# Power.net
KiCad netlist of a schematic drawn in Altium Designer
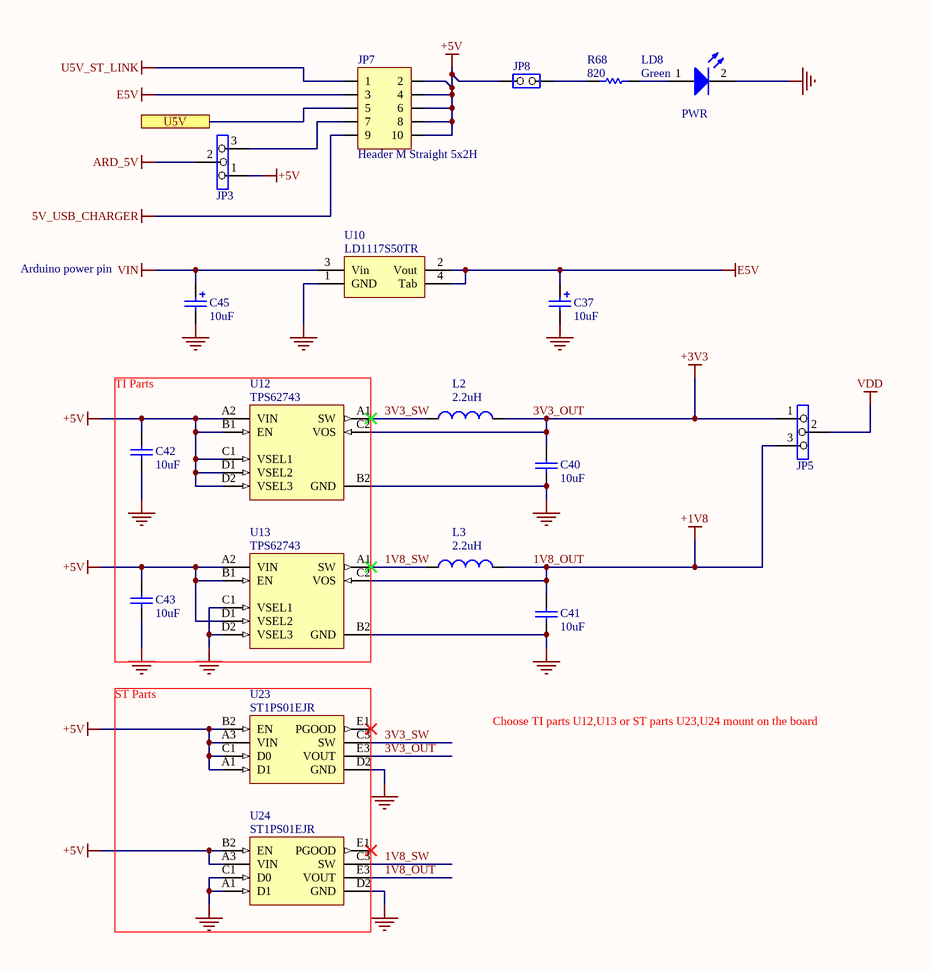
[diagram p0: Power.SchDoc]

(export (version "E")
  (design (tool "Eeschema 10.0.6"))
  (components
    (comp (ref "C37")
      (value "10uF")
      (footprint "TAN-A")
      (description "TAN Capacitor,10uF,10%,16V,A Type,AVX")
      (fields (field (name "Comment") "TAJA106K016R") (field (name "PUBLISHER") "Altium Limited"))
      (libsource (lib "Miscellaneous Devices") (part "Cap Pol1"))
    )
    (comp (ref "C40")
      (value "10uF")
      (footprint "0402C")
      (description "Capacitor,10uF,0402,GRM155R60J106ME11")
      (fields (field (name "Comment") "GRM155R60J106ME11") (field (name "PUBLISHER") "Altium Limited"))
      (libsource (lib "Miscellaneous Devices") (part "Cap"))
    )
    (comp (ref "C41")
      (value "10uF")
      (footprint "0402C")
      (description "Capacitor,10uF,0402,GRM155R60J106ME11")
      (fields (field (name "Comment") "GRM155R60J106ME11") (field (name "PUBLISHER") "Altium Limited"))
      (libsource (lib "Miscellaneous Devices") (part "Cap"))
    )
    (comp (ref "C42")
      (value "10uF")
      (footprint "0402C")
      (description "Capacitor,10uF,0402,GRM155R60J106ME11")
      (fields (field (name "Comment") "GRM155R60J106ME11") (field (name "PUBLISHER") "Altium Limited"))
      (libsource (lib "Miscellaneous Devices") (part "Cap"))
    )
    (comp (ref "C43")
      (value "10uF")
      (footprint "0402C")
      (description "Capacitor,10uF,0402,GRM155R60J106ME11")
      (fields (field (name "Comment") "GRM155R60J106ME11") (field (name "PUBLISHER") "Altium Limited"))
      (libsource (lib "Miscellaneous Devices") (part "Cap"))
    )
    (comp (ref "C45")
      (value "10uF")
      (footprint "TAN-B")
      (description "Tan Capacitor,10uF,10%,25V,Tan-B,TAJB106K025RNJ")
      (fields (field (name "Comment") "TAJB106K025RNJ") (field (name "PUBLISHER") "Altium Limited"))
      (libsource (lib "Miscellaneous Devices") (part "Cap Pol1"))
    )
    (comp (ref "JP3")
      (value "3 PIN Jumper")
      (footprint "SIP3")
      (libsource (lib "STR910_SCHLIB") (part "Jumper3"))
    )
    (comp (ref "JP5")
      (value "3 PIN Jumper")
      (footprint "SIP3")
      (libsource (lib "STR910_SCHLIB") (part "Jumper3"))
    )
    (comp (ref "JP7")
      (value "Header M Straight 5x2H")
      (footprint "HDR_2X5_2R54")
      (description "Pin Header male,2.54mm,2*5,L=11.6,180,1U,DIP")
      (libsource (lib "MCD_TOOLS_CONNECTOR") (part "Header 5X2M"))
    )
    (comp (ref "JP8") (value "2 PIN Jumper") (footprint "SIP2") (libsource (lib "*") (part "JP2")))
    (comp (ref "L2")
      (value "2.2uH")
      (footprint "L1008_L0805_CPT")
      (description "Inductor")
      (fields (field (name "PUBLISHER") "Altium Limited"))
      (libsource (lib "Miscellaneous Devices") (part "Inductor"))
    )
    (comp (ref "L3")
      (value "2.2uH")
      (footprint "L1008_L0805_CPT")
      (description "Inductor")
      (fields (field (name "PUBLISHER") "Altium Limited"))
      (libsource (lib "Miscellaneous Devices") (part "Inductor"))
    )
    (comp (ref "LD8")
      (value "19-213SY6C/S530-E2/TR8LED")
      (footprint "0603D")
      (description "LED,Green,0603")
      (fields
        (field (name "SILKSCREEN") "PWR")
        (field (name "CORLOR") "Green")
        (field (name "PUBLISHER") "Altium Limited")
      )
      (libsource (lib "Miscellaneous Devices") (part "LED2"))
    )
    (comp (ref "R68")
      (value "820")
      (footprint "0603R")
      (description "Resistor")
      (fields (field (name "PUBLISHER") "Altium Limited"))
      (libsource (lib "Miscellaneous Devices") (part "res1"))
    )
    (comp (ref "U10")
      (value "LD1117S50TR")
      (footprint "SOT-223")
      (description "Adjustable and fixed low drop positive voltage regulator")
      (libsource (lib "MB1219") (part "LD1117S18TR"))
    )
    (comp (ref "U12")
      (value "TPS62743")
      (footprint "BGA8_0R4_0R9X1R6")
      (description "High Efficiency Buck Converter")
      (libsource (lib "MB1261") (part "TPS62743"))
    )
    (comp (ref "U13")
      (value "TPS62743")
      (footprint "BGA8_0R4_0R9X1R6")
      (description "High Efficiency Buck Converter")
      (libsource (lib "MB1261") (part "TPS62743"))
    )
    (comp (ref "U23")
      (value "ST1PS01EJR")
      (footprint "BGA8_0R312-0R25_1R11X1R41")
      (description "400mA NanoQuiescent Step Down converter")
      (libsource (lib "Big Orga") (part "ST1PS01EJR"))
    )
    (comp (ref "U24")
      (value "ST1PS01EJR")
      (footprint "BGA8_0R312-0R25_1R11X1R41")
      (description "400mA NanoQuiescent Step Down converter")
      (libsource (lib "Big Orga") (part "ST1PS01EJR"))
    )
  )
  (nets
    (net (code "1") (name "+1V8") (class "Default")
      (node (ref "C41") (pin "1") (pinfunction "1_1") (pintype "passive"))
      (node (ref "JP5") (pin "3") (pintype "passive"))
      (node (ref "L3") (pin "2") (pinfunction "2_2") (pintype "passive"))
      (node (ref "U13") (pin "C2") (pinfunction "VOS_C2") (pintype "input"))
      (node (ref "U24") (pin "E3") (pinfunction "VOUT_E3") (pintype "power_in"))
    )
    (net (code "2") (name "+3V3") (class "Default")
      (node (ref "C40") (pin "1") (pinfunction "1_1") (pintype "passive"))
      (node (ref "JP5") (pin "1") (pintype "passive"))
      (node (ref "L2") (pin "2") (pinfunction "2_2") (pintype "passive"))
      (node (ref "U12") (pin "C2") (pinfunction "VOS_C2") (pintype "input"))
      (node (ref "U23") (pin "E3") (pinfunction "VOUT_E3") (pintype "power_in"))
    )
    (net (code "3") (name "+5V") (class "Default")
      (node (ref "C42") (pin "1") (pinfunction "1_1") (pintype "passive"))
      (node (ref "C43") (pin "1") (pinfunction "1_1") (pintype "passive"))
      (node (ref "JP3") (pin "1") (pintype "passive"))
      (node (ref "JP7") (pin "10") (pinfunction "10_10") (pintype "passive"))
      (node (ref "JP7") (pin "2") (pinfunction "2_2") (pintype "passive"))
      (node (ref "JP7") (pin "4") (pinfunction "4_4") (pintype "passive"))
      (node (ref "JP7") (pin "6") (pinfunction "6_6") (pintype "passive"))
      (node (ref "JP7") (pin "8") (pinfunction "8_8") (pintype "passive"))
      (node (ref "JP8") (pin "1") (pinfunction "COMMON_1") (pintype "passive"))
      (node (ref "U12") (pin "A2") (pinfunction "VIN_A2") (pintype "power_in"))
      (node (ref "U12") (pin "B1") (pinfunction "EN_B1") (pintype "input"))
      (node (ref "U12") (pin "C1") (pinfunction "VSEL1_C1") (pintype "input"))
      (node (ref "U12") (pin "D1") (pinfunction "VSEL2_D1") (pintype "input"))
      (node (ref "U12") (pin "D2") (pinfunction "VSEL3_D2") (pintype "input"))
      (node (ref "U13") (pin "A2") (pinfunction "VIN_A2") (pintype "power_in"))
      (node (ref "U13") (pin "B1") (pinfunction "EN_B1") (pintype "input"))
      (node (ref "U13") (pin "D1") (pinfunction "VSEL2_D1") (pintype "input"))
      (node (ref "U23") (pin "A1") (pinfunction "D1_A1") (pintype "input"))
      (node (ref "U23") (pin "A3") (pinfunction "VIN_A3") (pintype "power_in"))
      (node (ref "U23") (pin "B2") (pinfunction "EN_B2") (pintype "input"))
      (node (ref "U23") (pin "C1") (pinfunction "D0_C1") (pintype "input"))
      (node (ref "U24") (pin "A3") (pinfunction "VIN_A3") (pintype "power_in"))
      (node (ref "U24") (pin "B2") (pinfunction "EN_B2") (pintype "input"))
    )
    (net (code "4") (name "/1V8_SW") (class "Default")
      (node (ref "L3") (pin "1") (pinfunction "1_1") (pintype "passive"))
      (node (ref "U13") (pin "A1") (pinfunction "SW_A1") (pintype "output"))
      (node (ref "U24") (pin "C3") (pinfunction "SW_C3") (pintype "power_in"))
    )
    (net (code "5") (name "/3V3_SW") (class "Default")
      (node (ref "L2") (pin "1") (pinfunction "1_1") (pintype "passive"))
      (node (ref "U12") (pin "A1") (pinfunction "SW_A1") (pintype "output"))
      (node (ref "U23") (pin "C3") (pinfunction "SW_C3") (pintype "power_in"))
    )
    (net (code "6") (name "/U5V") (class "Default")
      (node (ref "JP7") (pin "5") (pinfunction "5_5") (pintype "passive"))
    )
    (net (code "7") (name "5V_USB_CHARGER") (class "Default")
      (node (ref "JP7") (pin "9") (pinfunction "9_9") (pintype "passive"))
    )
    (net (code "8") (name "ARD_5V") (class "Default") (node (ref "JP3") (pin "2") (pintype "passive")))
    (net (code "9") (name "E5V") (class "Default")
      (node (ref "C37") (pin "1") (pinfunction "1_1") (pintype "passive"))
      (node (ref "JP7") (pin "3") (pinfunction "3_3") (pintype "passive"))
      (node (ref "U10") (pin "2") (pinfunction "Vout_2") (pintype "power_in"))
      (node (ref "U10") (pin "4") (pinfunction "Tab_4") (pintype "power_in"))
    )
    (net (code "10") (name "GND") (class "Default")
      (node (ref "C37") (pin "2") (pinfunction "2_2") (pintype "passive"))
      (node (ref "C40") (pin "2") (pinfunction "2_2") (pintype "passive"))
      (node (ref "C41") (pin "2") (pinfunction "2_2") (pintype "passive"))
      (node (ref "C42") (pin "2") (pinfunction "2_2") (pintype "passive"))
      (node (ref "C43") (pin "2") (pinfunction "2_2") (pintype "passive"))
      (node (ref "C45") (pin "2") (pinfunction "2_2") (pintype "passive"))
      (node (ref "LD8") (pin "2") (pinfunction "K_2") (pintype "passive"))
      (node (ref "U10") (pin "1") (pinfunction "GND_1") (pintype "power_in"))
      (node (ref "U12") (pin "B2") (pinfunction "GND_B2") (pintype "power_in"))
      (node (ref "U13") (pin "B2") (pinfunction "GND_B2") (pintype "power_in"))
      (node (ref "U13") (pin "C1") (pinfunction "VSEL1_C1") (pintype "input"))
      (node (ref "U13") (pin "D2") (pinfunction "VSEL3_D2") (pintype "input"))
      (node (ref "U23") (pin "D2") (pinfunction "GND_D2") (pintype "power_in"))
      (node (ref "U24") (pin "A1") (pinfunction "D1_A1") (pintype "input"))
      (node (ref "U24") (pin "C1") (pinfunction "D0_C1") (pintype "input"))
      (node (ref "U24") (pin "D2") (pinfunction "GND_D2") (pintype "power_in"))
    )
    (net (code "11") (name "Net-(JP3-Pad3)") (class "Default")
      (node (ref "JP3") (pin "3") (pintype "passive"))
      (node (ref "JP7") (pin "7") (pinfunction "7_7") (pintype "passive"))
    )
    (net (code "12") (name "Net-(JP8-NO)") (class "Default")
      (node (ref "JP8") (pin "2") (pinfunction "NO_2") (pintype "passive"))
      (node (ref "R68") (pin "2") (pinfunction "2_2") (pintype "passive"))
    )
    (net (code "13") (name "Net-(LD8-A)") (class "Default")
      (node (ref "LD8") (pin "1") (pinfunction "A_1") (pintype "passive"))
      (node (ref "R68") (pin "1") (pinfunction "1_1") (pintype "passive"))
    )
    (net (code "14") (name "U5V_ST_LINK") (class "Default")
      (node (ref "JP7") (pin "1") (pinfunction "1_1") (pintype "passive"))
    )
    (net (code "15") (name "VDD") (class "Default") (node (ref "JP5") (pin "2") (pintype "passive")))
    (net (code "16") (name "VIN") (class "Default")
      (node (ref "C45") (pin "1") (pinfunction "1_1") (pintype "passive"))
      (node (ref "U10") (pin "3") (pinfunction "Vin_3") (pintype "power_in"))
    )
    (net (code "17") (name "unconnected-(U23-PGOOD-PadE1)") (class "Default")
      (node (ref "U23") (pin "E1") (pinfunction "PGOOD_E1") (pintype "output+no_connect"))
    )
    (net (code "18") (name "unconnected-(U24-PGOOD-PadE1)") (class "Default")
      (node (ref "U24") (pin "E1") (pinfunction "PGOOD_E1") (pintype "output+no_connect"))
    )
  )
)
